# WhiteDwarf_Core.net
KiCad netlist of a schematic drawn in EAGLE
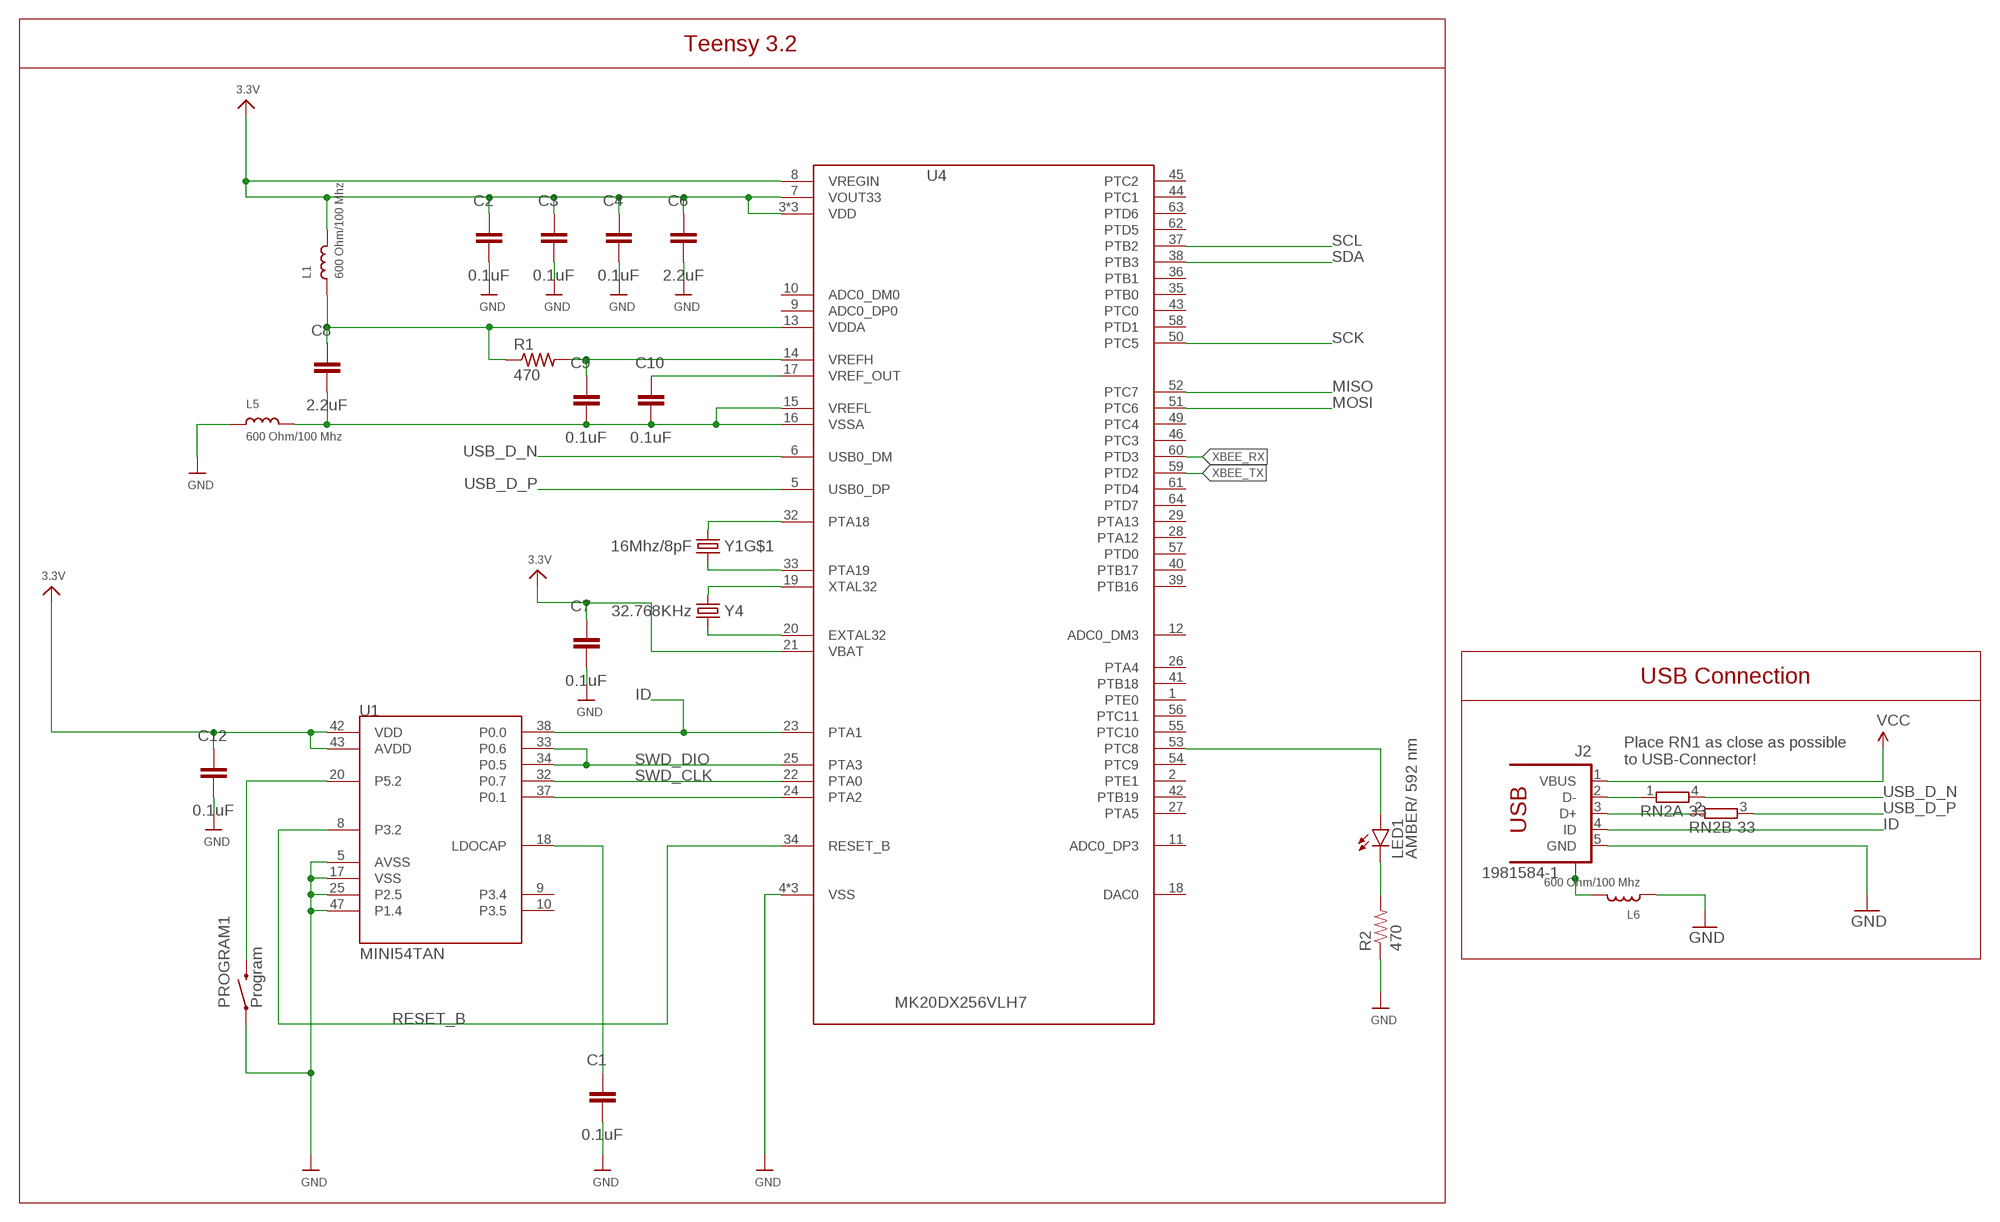
[diagram p0: schematic, sheet 1]

(export (version "E")
  (design (tool "Eeschema 10.0.6"))
  (components
    (comp (ref "C1")
      (value "0.1uF")
      (footprint "eagle-import:CAP_0402")
      (fields
        (field (name "DIGIKEY_PART_NUMBER") "311-1014-2-ND")
        (field (name "MANUFACTURER") "Yageo")
        (field (name "MPN") "CC0402JRNPO9BN100")
        (field (name "CREATED_BY") "PCBLayout.com")
      )
      (libsource (lib "eagle-import") (part "CC0402JRNPO9BN100"))
    )
    (comp (ref "C2")
      (value "0.1uF")
      (footprint "eagle-import:CAP_0402")
      (fields
        (field (name "DIGIKEY_PART_NUMBER") "311-1014-2-ND")
        (field (name "MANUFACTURER") "Yageo")
        (field (name "MPN") "CC0402JRNPO9BN100")
        (field (name "CREATED_BY") "PCBLayout.com")
      )
      (libsource (lib "eagle-import") (part "CC0402JRNPO9BN100"))
    )
    (comp (ref "C3")
      (value "0.1uF")
      (footprint "eagle-import:CAP_0402")
      (fields
        (field (name "DIGIKEY_PART_NUMBER") "311-1014-2-ND")
        (field (name "MANUFACTURER") "Yageo")
        (field (name "MPN") "CC0402JRNPO9BN100")
        (field (name "CREATED_BY") "PCBLayout.com")
      )
      (libsource (lib "eagle-import") (part "CC0402JRNPO9BN100"))
    )
    (comp (ref "C4")
      (value "0.1uF")
      (footprint "eagle-import:CAP_0402")
      (fields
        (field (name "DIGIKEY_PART_NUMBER") "311-1014-2-ND")
        (field (name "MANUFACTURER") "Yageo")
        (field (name "MPN") "CC0402JRNPO9BN100")
        (field (name "CREATED_BY") "PCBLayout.com")
      )
      (libsource (lib "eagle-import") (part "CC0402JRNPO9BN100"))
    )
    (comp (ref "C6")
      (value "2.2uF")
      (footprint "eagle-import:CAP_0402")
      (fields
        (field (name "DIGIKEY_PART_NUMBER") "311-1018-2-ND")
        (field (name "MANUFACTURER") "Yageo")
        (field (name "MPN") "CC0402JRNPO9BN220")
        (field (name "CREATED_BY") "PCBLayout.com")
      )
      (libsource (lib "eagle-import") (part "CC0402JRNPO9BN220"))
    )
    (comp (ref "C7")
      (value "0.1uF")
      (footprint "eagle-import:CAP_0402")
      (fields
        (field (name "DIGIKEY_PART_NUMBER") "311-1014-2-ND")
        (field (name "MANUFACTURER") "Yageo")
        (field (name "MPN") "CC0402JRNPO9BN100")
        (field (name "CREATED_BY") "PCBLayout.com")
      )
      (libsource (lib "eagle-import") (part "CC0402JRNPO9BN100"))
    )
    (comp (ref "C8")
      (value "2.2uF")
      (footprint "eagle-import:CAP_0402")
      (fields
        (field (name "DIGIKEY_PART_NUMBER") "311-1014-2-ND")
        (field (name "MANUFACTURER") "Yageo")
        (field (name "MPN") "CC0402JRNPO9BN100")
        (field (name "CREATED_BY") "PCBLayout.com")
      )
      (libsource (lib "eagle-import") (part "CC0402JRNPO9BN100"))
    )
    (comp (ref "C9")
      (value "0.1uF")
      (footprint "eagle-import:CAP_0402")
      (fields
        (field (name "DIGIKEY_PART_NUMBER") "311-1014-2-ND")
        (field (name "MANUFACTURER") "Yageo")
        (field (name "MPN") "CC0402JRNPO9BN100")
        (field (name "CREATED_BY") "PCBLayout.com")
      )
      (libsource (lib "eagle-import") (part "CC0402JRNPO9BN100"))
    )
    (comp (ref "C10")
      (value "0.1uF")
      (footprint "eagle-import:CAP_0402")
      (fields
        (field (name "DIGIKEY_PART_NUMBER") "311-1014-2-ND")
        (field (name "MANUFACTURER") "Yageo")
        (field (name "MPN") "CC0402JRNPO9BN100")
        (field (name "CREATED_BY") "PCBLayout.com")
      )
      (libsource (lib "eagle-import") (part "CC0402JRNPO9BN100"))
    )
    (comp (ref "C12")
      (value "0.1uF")
      (footprint "eagle-import:CAP_0402")
      (fields
        (field (name "DIGIKEY_PART_NUMBER") "311-1014-2-ND")
        (field (name "MANUFACTURER") "Yageo")
        (field (name "MPN") "CC0402JRNPO9BN100")
        (field (name "CREATED_BY") "PCBLayout.com")
      )
      (libsource (lib "eagle-import") (part "CC0402JRNPO9BN100"))
    )
    (comp (ref "J2")
      (value "1981584-1")
      (footprint "eagle-import:1981584-1")
      (fields (field (name "MF") "Hirose") (field (name "MPN") "ZX62-AB-5PA(11) "))
      (libsource (lib "eagle-import") (part "1981584-1"))
    )
    (comp (ref "L1")
      (value "600 Ohm/100 Mhz")
      (footprint "eagle-import:0805")
      (fields (field (name "MF") "Taiyo Yuden") (field (name "MPN") "BK2125HM601-T"))
      (libsource (lib "eagle-import") (part "INDUCTOR-BK2125HM601-T"))
    )
    (comp (ref "L5")
      (value "600 Ohm/100 Mhz")
      (footprint "eagle-import:0805")
      (fields (field (name "MF") "Taiyo Yuden") (field (name "MPN") "BK2125HM601-T"))
      (libsource (lib "eagle-import") (part "INDUCTOR-BK2125HM601-T"))
    )
    (comp (ref "L6")
      (value "600 Ohm/100 Mhz")
      (footprint "eagle-import:0805")
      (fields (field (name "MF") "Taiyo Yuden") (field (name "MPN") "BK2125HM601-T"))
      (libsource (lib "eagle-import") (part "INDUCTOR-BK2125HM601-T"))
    )
    (comp (ref "LED1")
      (value "AMBER/ 592 nm")
      (footprint "eagle-import:LED-0603")
      (fields (field (name "MF") "Avago Technologies") (field (name "MPN") "HSMA-C190"))
      (libsource (lib "eagle-import") (part "LED-AMBER"))
    )
    (comp (ref "PROGRAM1")
      (value "Program")
      (footprint "eagle-import:TACTILE-SWITCH-1101NE")
      (fields (field (name "MF") "C&K Components") (field (name "MPN") "RS-282G05A3-SM RT"))
      (libsource (lib "eagle-import") (part "SWITCH-MOMENTARY-2-SMD-1101NE"))
    )
    (comp (ref "R1")
      (value "470")
      (footprint "eagle-import:RES_0402")
      (fields
        (field (name "DIGIKEY_PART_NUMBER") "311-0.0JRTR-ND")
        (field (name "MANUFACTURER") "Yageo")
        (field (name "MPN") "RC0402JR-070RL")
        (field (name "CREATED_BY") "PCBLayout.com")
      )
      (libsource (lib "eagle-import") (part "RC0402JR-070RL"))
    )
    (comp (ref "R2")
      (value "470")
      (footprint "eagle-import:0603-RES")
      (fields (field (name "MF") "Panasonic") (field (name "MPN") "ERJ-3GEYJ471V"))
      (libsource (lib "eagle-import") (part "RESISTOR-470"))
    )
    (comp (ref "RN2")
      (value "33")
      (footprint "eagle-import:EXB34V")
      (fields (field (name "MF") "Panasonic") (field (name "MPN") "EXB-34V330JV"))
      (libsource (lib "eagle-import") (part "2R-NEXB34V"))
    )
    (comp (ref "U1")
      (value "MINI54TAN")
      (footprint "eagle-import:MINI54TAN")
      (libsource (lib "eagle-import") (part "MINI54TAN"))
    )
    (comp (ref "U4")
      (value "MK20DX256VLH7")
      (footprint "eagle-import:MK20DX256VLH7")
      (fields (field (name "MF") "Freescale"))
      (libsource (lib "eagle-import") (part "MK20DX256VLH7"))
    )
    (comp (ref "Y1")
      (value "16Mhz/8pF")
      (footprint "eagle-import:CRYSTAL-SMD-5X3")
      (fields (field (name "MF") "ECS") (field (name "MPN") "ECS-160-8-30B-CKM"))
      (libsource (lib "eagle-import") (part "CRYSTAL/SMD-5X3-GND16MHZ/8PF"))
    )
    (comp (ref "Y4")
      (value "32.768KHz")
      (footprint "eagle-import:CRYSTAL-TXC-7A")
      (fields (field (name "MF") "Epson Timing") (field (name "MPN") "FC-255 32.7680K-A3"))
      (libsource (lib "eagle-import") (part "CRYSTAL/32.768KHZ/SMD-TXC_7A"))
    )
  )
  (nets
    (net (code "1") (name "/ID") (class "Default")
      (node (ref "J2") (pin "4") (pinfunction "ID_4") (pintype "passive"))
      (node (ref "U1") (pin "38") (pinfunction "P0.0_38") (pintype "bidirectional"))
      (node (ref "U4") (pin "23") (pinfunction "PTA1_23") (pintype "bidirectional"))
    )
    (net (code "2") (name "/MISO") (class "Default")
      (node (ref "U4") (pin "52") (pinfunction "PTC7_52") (pintype "bidirectional"))
    )
    (net (code "3") (name "/MOSI") (class "Default")
      (node (ref "U4") (pin "51") (pinfunction "PTC6_51") (pintype "bidirectional"))
    )
    (net (code "4") (name "/RESET_B") (class "Default")
      (node (ref "U1") (pin "8") (pinfunction "P3.2_8") (pintype "bidirectional"))
      (node (ref "U4") (pin "34") (pinfunction "RESET_B_34") (pintype "bidirectional"))
    )
    (net (code "5") (name "/SCK") (class "Default")
      (node (ref "U4") (pin "50") (pinfunction "PTC5_50") (pintype "bidirectional"))
    )
    (net (code "6") (name "/SCL") (class "Default")
      (node (ref "U4") (pin "37") (pinfunction "PTB2_37") (pintype "bidirectional"))
    )
    (net (code "7") (name "/SDA") (class "Default")
      (node (ref "U4") (pin "38") (pinfunction "PTB3_38") (pintype "bidirectional"))
    )
    (net (code "8") (name "/SWD_CLK") (class "Default")
      (node (ref "U1") (pin "32") (pinfunction "P0.7_32") (pintype "bidirectional"))
      (node (ref "U4") (pin "22") (pinfunction "PTA0_22") (pintype "bidirectional"))
    )
    (net (code "9") (name "/SWD_DIO") (class "Default")
      (node (ref "U1") (pin "33") (pinfunction "P0.6_33") (pintype "bidirectional"))
      (node (ref "U1") (pin "34") (pinfunction "P0.5_34") (pintype "bidirectional"))
      (node (ref "U4") (pin "25") (pinfunction "PTA3_25") (pintype "bidirectional"))
    )
    (net (code "10") (name "/USB_D_N") (class "Default")
      (node (ref "RN2") (pin "4") (pinfunction "2_4") (pintype "passive"))
      (node (ref "U4") (pin "6") (pinfunction "USB0_DM_6") (pintype "bidirectional"))
    )
    (net (code "11") (name "/USB_D_P") (class "Default")
      (node (ref "RN2") (pin "3") (pinfunction "2_3") (pintype "passive"))
      (node (ref "U4") (pin "5") (pinfunction "USB0_DP_5") (pintype "bidirectional"))
    )
    (net (code "12") (name "3.3V") (class "Default")
      (node (ref "C12") (pin "1") (pinfunction "1_1") (pintype "passive"))
      (node (ref "C2") (pin "1") (pinfunction "1_1") (pintype "passive"))
      (node (ref "C3") (pin "1") (pinfunction "1_1") (pintype "passive"))
      (node (ref "C4") (pin "1") (pinfunction "1_1") (pintype "passive"))
      (node (ref "C6") (pin "1") (pinfunction "1_1") (pintype "passive"))
      (node (ref "C7") (pin "1") (pinfunction "1_1") (pintype "passive"))
      (node (ref "L1") (pin "2") (pinfunction "2_2") (pintype "passive"))
      (node (ref "U1") (pin "42") (pinfunction "VDD_42") (pintype "bidirectional"))
      (node (ref "U1") (pin "43") (pinfunction "AVDD_43") (pintype "bidirectional"))
      (node (ref "U4") (pin "21") (pinfunction "VBAT_21") (pintype "bidirectional"))
      (node (ref "U4") (pin "3") (pinfunction "VDD_3") (pintype "bidirectional"))
      (node (ref "U4") (pin "30") (pinfunction "VDD_30") (pintype "bidirectional"))
      (node (ref "U4") (pin "48") (pinfunction "VDD_48") (pintype "bidirectional"))
      (node (ref "U4") (pin "7") (pinfunction "VOUT33_7") (pintype "bidirectional"))
      (node (ref "U4") (pin "8") (pinfunction "VREGIN_8") (pintype "bidirectional"))
    )
    (net (code "13") (name "GND") (class "Default")
      (node (ref "C1") (pin "2") (pinfunction "2_2") (pintype "passive"))
      (node (ref "C12") (pin "2") (pinfunction "2_2") (pintype "passive"))
      (node (ref "C2") (pin "2") (pinfunction "2_2") (pintype "passive"))
      (node (ref "C3") (pin "2") (pinfunction "2_2") (pintype "passive"))
      (node (ref "C4") (pin "2") (pinfunction "2_2") (pintype "passive"))
      (node (ref "C6") (pin "2") (pinfunction "2_2") (pintype "passive"))
      (node (ref "C7") (pin "2") (pinfunction "2_2") (pintype "passive"))
      (node (ref "J2") (pin "5") (pinfunction "GND_5") (pintype "passive"))
      (node (ref "L5") (pin "1") (pinfunction "1_1") (pintype "passive"))
      (node (ref "L6") (pin "1") (pinfunction "1_1") (pintype "passive"))
      (node (ref "PROGRAM1") (pin "P$1") (pinfunction "1_P$1") (pintype "passive"))
      (node (ref "R2") (pin "1") (pinfunction "1_1") (pintype "passive"))
      (node (ref "U1") (pin "17") (pinfunction "VSS_17") (pintype "bidirectional"))
      (node (ref "U1") (pin "25") (pinfunction "P2.5_25") (pintype "bidirectional"))
      (node (ref "U1") (pin "47") (pinfunction "P1.4_47") (pintype "bidirectional"))
      (node (ref "U1") (pin "5") (pinfunction "AVSS_5") (pintype "bidirectional"))
      (node (ref "U4") (pin "31") (pinfunction "VSS_31") (pintype "bidirectional"))
      (node (ref "U4") (pin "4") (pinfunction "VSS_4") (pintype "bidirectional"))
      (node (ref "U4") (pin "47") (pinfunction "VSS_47") (pintype "bidirectional"))
    )
    (net (code "14") (name "Net-(J2-D+)") (class "Default")
      (node (ref "J2") (pin "3") (pinfunction "D+_3") (pintype "passive"))
      (node (ref "RN2") (pin "2") (pinfunction "1_2") (pintype "passive"))
    )
    (net (code "15") (name "Net-(J2-D-)") (class "Default")
      (node (ref "J2") (pin "2") (pinfunction "D-_2") (pintype "passive"))
      (node (ref "RN2") (pin "1") (pinfunction "1_1") (pintype "passive"))
    )
    (net (code "16") (name "Net-(J2-PadS1)") (class "Default")
      (node (ref "J2") (pin "S1") (pinfunction "S1_S1") (pintype "passive"))
      (node (ref "J2") (pin "S2") (pinfunction "S2_S2") (pintype "passive"))
      (node (ref "J2") (pin "S3") (pinfunction "S3_S3") (pintype "passive"))
      (node (ref "J2") (pin "S4") (pinfunction "S4_S4") (pintype "passive"))
      (node (ref "L6") (pin "2") (pinfunction "2_2") (pintype "passive"))
    )
    (net (code "17") (name "Net-(LED1-PadC)") (class "Default")
      (node (ref "LED1") (pin "C") (pinfunction "C_C") (pintype "passive"))
      (node (ref "R2") (pin "2") (pinfunction "2_2") (pintype "passive"))
    )
    (net (code "18") (name "Net-(PROGRAM1-2)") (class "Default")
      (node (ref "PROGRAM1") (pin "P$2") (pinfunction "2_P$2") (pintype "passive"))
      (node (ref "U1") (pin "20") (pinfunction "P5.2_20") (pintype "bidirectional"))
    )
    (net (code "19") (name "Net-(U1-LDOCAP)") (class "Default")
      (node (ref "C1") (pin "1") (pinfunction "1_1") (pintype "passive"))
      (node (ref "U1") (pin "18") (pinfunction "LDOCAP_18") (pintype "bidirectional"))
    )
    (net (code "20") (name "Net-(U1-P0.1)") (class "Default")
      (node (ref "U1") (pin "37") (pinfunction "P0.1_37") (pintype "bidirectional"))
      (node (ref "U4") (pin "24") (pinfunction "PTA2_24") (pintype "bidirectional"))
    )
    (net (code "21") (name "Net-(U4-EXTAL32)") (class "Default")
      (node (ref "U4") (pin "20") (pinfunction "EXTAL32_20") (pintype "bidirectional"))
      (node (ref "Y4") (pin "P$1") (pinfunction "1_P$1") (pintype "passive"))
    )
    (net (code "22") (name "Net-(U4-PTA18)") (class "Default")
      (node (ref "U4") (pin "32") (pinfunction "PTA18_32") (pintype "bidirectional"))
      (node (ref "Y1") (pin "3") (pinfunction "2_3") (pintype "passive"))
    )
    (net (code "23") (name "Net-(U4-PTA19)") (class "Default")
      (node (ref "U4") (pin "33") (pinfunction "PTA19_33") (pintype "bidirectional"))
      (node (ref "Y1") (pin "1") (pinfunction "1_1") (pintype "passive"))
    )
    (net (code "24") (name "Net-(U4-PTC8)") (class "Default")
      (node (ref "LED1") (pin "A") (pinfunction "A_A") (pintype "passive"))
      (node (ref "U4") (pin "53") (pinfunction "PTC8_53") (pintype "bidirectional"))
    )
    (net (code "25") (name "Net-(U4-VDDA)") (class "Default")
      (node (ref "C8") (pin "1") (pinfunction "1_1") (pintype "passive"))
      (node (ref "L1") (pin "1") (pinfunction "1_1") (pintype "passive"))
      (node (ref "R1") (pin "1") (pinfunction "1_1") (pintype "passive"))
      (node (ref "U4") (pin "13") (pinfunction "VDDA_13") (pintype "bidirectional"))
    )
    (net (code "26") (name "Net-(U4-VREFH)") (class "Default")
      (node (ref "C9") (pin "1") (pinfunction "1_1") (pintype "passive"))
      (node (ref "R1") (pin "2") (pinfunction "2_2") (pintype "passive"))
      (node (ref "U4") (pin "14") (pinfunction "VREFH_14") (pintype "bidirectional"))
    )
    (net (code "27") (name "Net-(U4-VREFL)") (class "Default")
      (node (ref "C10") (pin "2") (pinfunction "2_2") (pintype "passive"))
      (node (ref "C8") (pin "2") (pinfunction "2_2") (pintype "passive"))
      (node (ref "C9") (pin "2") (pinfunction "2_2") (pintype "passive"))
      (node (ref "L5") (pin "2") (pinfunction "2_2") (pintype "passive"))
      (node (ref "U4") (pin "15") (pinfunction "VREFL_15") (pintype "bidirectional"))
      (node (ref "U4") (pin "16") (pinfunction "VSSA_16") (pintype "bidirectional"))
    )
    (net (code "28") (name "Net-(U4-VREF_OUT)") (class "Default")
      (node (ref "C10") (pin "1") (pinfunction "1_1") (pintype "passive"))
      (node (ref "U4") (pin "17") (pinfunction "VREF_OUT_17") (pintype "bidirectional"))
    )
    (net (code "29") (name "Net-(U4-XTAL32)") (class "Default")
      (node (ref "U4") (pin "19") (pinfunction "XTAL32_19") (pintype "bidirectional"))
      (node (ref "Y4") (pin "P$2") (pinfunction "2_P$2") (pintype "passive"))
    )
    (net (code "30") (name "VCC") (class "Default")
      (node (ref "J2") (pin "1") (pinfunction "VBUS_1") (pintype "passive"))
    )
    (net (code "31") (name "XBEE_RX") (class "Default")
      (node (ref "U4") (pin "60") (pinfunction "PTD3_60") (pintype "bidirectional"))
    )
    (net (code "32") (name "XBEE_TX") (class "Default")
      (node (ref "U4") (pin "59") (pinfunction "PTD2_59") (pintype "bidirectional"))
    )
    (net (code "33") (name "unconnected-(U1-P3.4-Pad9)") (class "Default")
      (node (ref "U1") (pin "9") (pinfunction "P3.4_9") (pintype "bidirectional"))
    )
    (net (code "34") (name "unconnected-(U1-P3.5-Pad10)") (class "Default")
      (node (ref "U1") (pin "10") (pinfunction "P3.5_10") (pintype "bidirectional"))
    )
    (net (code "35") (name "unconnected-(U4-ADC0_DM0-Pad10)") (class "Default")
      (node (ref "U4") (pin "10") (pinfunction "ADC0_DM0_10") (pintype "bidirectional"))
    )
    (net (code "36") (name "unconnected-(U4-ADC0_DM3-Pad12)") (class "Default")
      (node (ref "U4") (pin "12") (pinfunction "ADC0_DM3_12") (pintype "bidirectional"))
    )
    (net (code "37") (name "unconnected-(U4-ADC0_DP0-Pad9)") (class "Default")
      (node (ref "U4") (pin "9") (pinfunction "ADC0_DP0_9") (pintype "bidirectional"))
    )
    (net (code "38") (name "unconnected-(U4-ADC0_DP3-Pad11)") (class "Default")
      (node (ref "U4") (pin "11") (pinfunction "ADC0_DP3_11") (pintype "bidirectional"))
    )
    (net (code "39") (name "unconnected-(U4-DAC0-Pad18)") (class "Default")
      (node (ref "U4") (pin "18") (pinfunction "DAC0_18") (pintype "bidirectional"))
    )
    (net (code "40") (name "unconnected-(U4-PTA4-Pad26)") (class "Default")
      (node (ref "U4") (pin "26") (pinfunction "PTA4_26") (pintype "bidirectional"))
    )
    (net (code "41") (name "unconnected-(U4-PTA5-Pad27)") (class "Default")
      (node (ref "U4") (pin "27") (pinfunction "PTA5_27") (pintype "bidirectional"))
    )
    (net (code "42") (name "unconnected-(U4-PTA12-Pad28)") (class "Default")
      (node (ref "U4") (pin "28") (pinfunction "PTA12_28") (pintype "bidirectional"))
    )
    (net (code "43") (name "unconnected-(U4-PTA13-Pad29)") (class "Default")
      (node (ref "U4") (pin "29") (pinfunction "PTA13_29") (pintype "bidirectional"))
    )
    (net (code "44") (name "unconnected-(U4-PTB0-Pad35)") (class "Default")
      (node (ref "U4") (pin "35") (pinfunction "PTB0_35") (pintype "bidirectional"))
    )
    (net (code "45") (name "unconnected-(U4-PTB1-Pad36)") (class "Default")
      (node (ref "U4") (pin "36") (pinfunction "PTB1_36") (pintype "bidirectional"))
    )
    (net (code "46") (name "unconnected-(U4-PTB16-Pad39)") (class "Default")
      (node (ref "U4") (pin "39") (pinfunction "PTB16_39") (pintype "bidirectional"))
    )
    (net (code "47") (name "unconnected-(U4-PTB17-Pad40)") (class "Default")
      (node (ref "U4") (pin "40") (pinfunction "PTB17_40") (pintype "bidirectional"))
    )
    (net (code "48") (name "unconnected-(U4-PTB18-Pad41)") (class "Default")
      (node (ref "U4") (pin "41") (pinfunction "PTB18_41") (pintype "bidirectional"))
    )
    (net (code "49") (name "unconnected-(U4-PTB19-Pad42)") (class "Default")
      (node (ref "U4") (pin "42") (pinfunction "PTB19_42") (pintype "bidirectional"))
    )
    (net (code "50") (name "unconnected-(U4-PTC0-Pad43)") (class "Default")
      (node (ref "U4") (pin "43") (pinfunction "PTC0_43") (pintype "bidirectional"))
    )
    (net (code "51") (name "unconnected-(U4-PTC1-Pad44)") (class "Default")
      (node (ref "U4") (pin "44") (pinfunction "PTC1_44") (pintype "bidirectional"))
    )
    (net (code "52") (name "unconnected-(U4-PTC2-Pad45)") (class "Default")
      (node (ref "U4") (pin "45") (pinfunction "PTC2_45") (pintype "bidirectional"))
    )
    (net (code "53") (name "unconnected-(U4-PTC3-Pad46)") (class "Default")
      (node (ref "U4") (pin "46") (pinfunction "PTC3_46") (pintype "bidirectional"))
    )
    (net (code "54") (name "unconnected-(U4-PTC4-Pad49)") (class "Default")
      (node (ref "U4") (pin "49") (pinfunction "PTC4_49") (pintype "bidirectional"))
    )
    (net (code "55") (name "unconnected-(U4-PTC9-Pad54)") (class "Default")
      (node (ref "U4") (pin "54") (pinfunction "PTC9_54") (pintype "bidirectional"))
    )
    (net (code "56") (name "unconnected-(U4-PTC10-Pad55)") (class "Default")
      (node (ref "U4") (pin "55") (pinfunction "PTC10_55") (pintype "bidirectional"))
    )
    (net (code "57") (name "unconnected-(U4-PTC11-Pad56)") (class "Default")
      (node (ref "U4") (pin "56") (pinfunction "PTC11_56") (pintype "bidirectional"))
    )
    (net (code "58") (name "unconnected-(U4-PTD0-Pad57)") (class "Default")
      (node (ref "U4") (pin "57") (pinfunction "PTD0_57") (pintype "bidirectional"))
    )
    (net (code "59") (name "unconnected-(U4-PTD1-Pad58)") (class "Default")
      (node (ref "U4") (pin "58") (pinfunction "PTD1_58") (pintype "bidirectional"))
    )
    (net (code "60") (name "unconnected-(U4-PTD4-Pad61)") (class "Default")
      (node (ref "U4") (pin "61") (pinfunction "PTD4_61") (pintype "bidirectional"))
    )
    (net (code "61") (name "unconnected-(U4-PTD5-Pad62)") (class "Default")
      (node (ref "U4") (pin "62") (pinfunction "PTD5_62") (pintype "bidirectional"))
    )
    (net (code "62") (name "unconnected-(U4-PTD6-Pad63)") (class "Default")
      (node (ref "U4") (pin "63") (pinfunction "PTD6_63") (pintype "bidirectional"))
    )
    (net (code "63") (name "unconnected-(U4-PTD7-Pad64)") (class "Default")
      (node (ref "U4") (pin "64") (pinfunction "PTD7_64") (pintype "bidirectional"))
    )
    (net (code "64") (name "unconnected-(U4-PTE0-Pad1)") (class "Default")
      (node (ref "U4") (pin "1") (pinfunction "PTE0_1") (pintype "bidirectional"))
    )
    (net (code "65") (name "unconnected-(U4-PTE1-Pad2)") (class "Default")
      (node (ref "U4") (pin "2") (pinfunction "PTE1_2") (pintype "bidirectional"))
    )
  )
)
